# Sheet1_Palm.net
KiCad netlist of a schematic drawn in Altium Designer
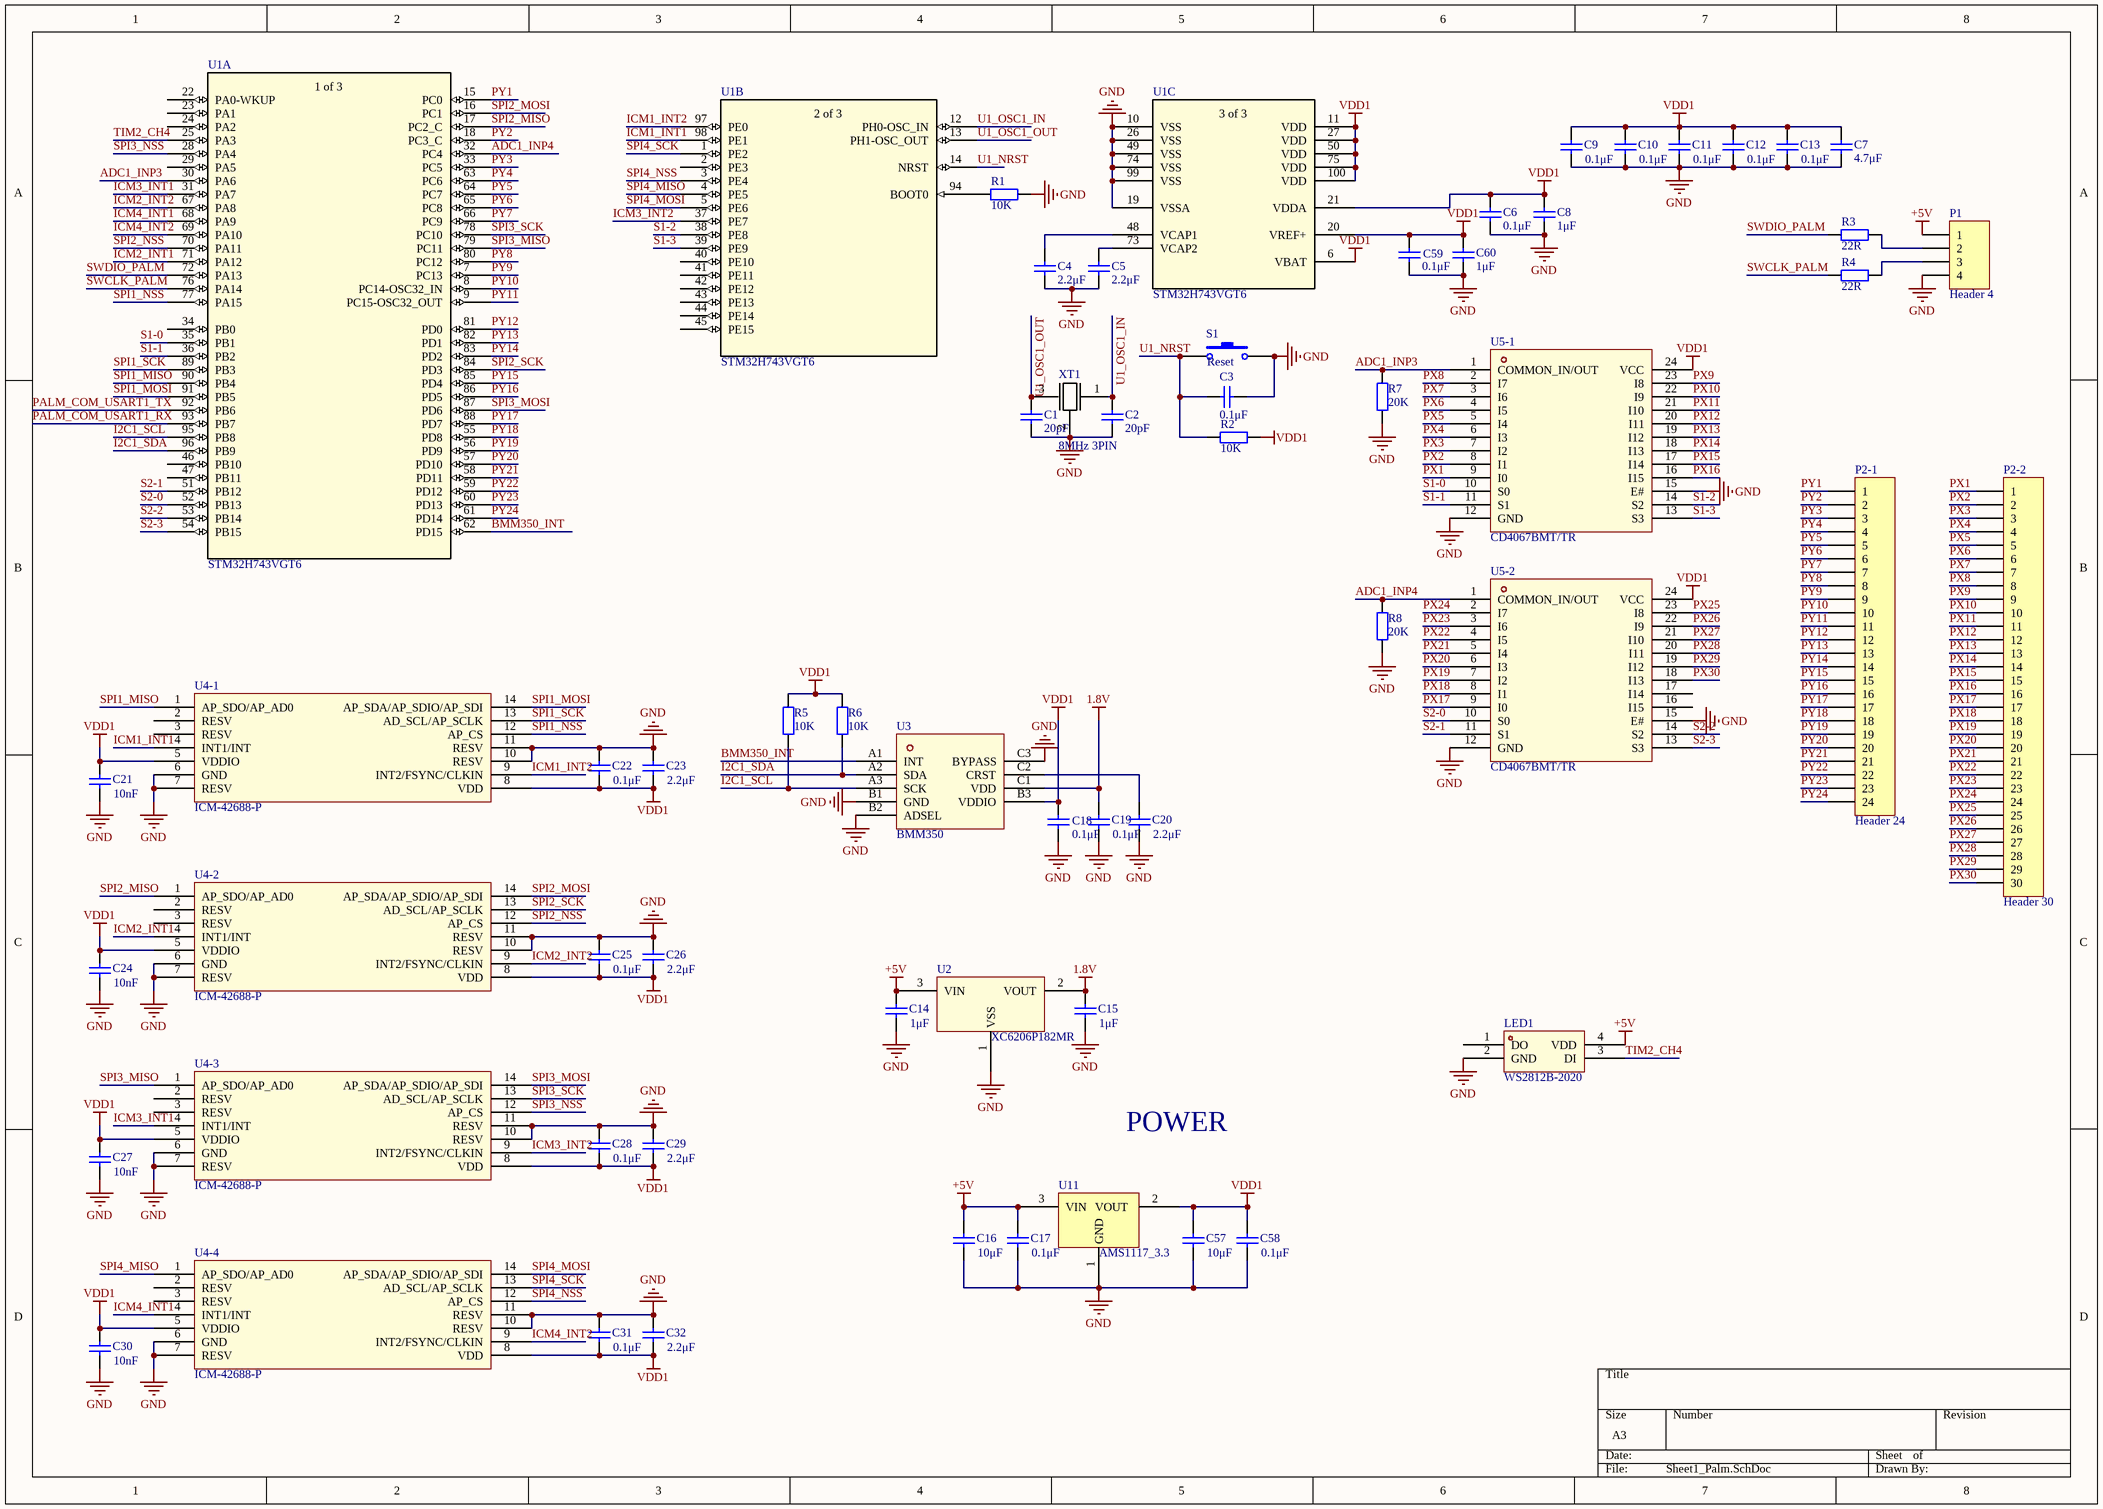
[diagram p0: Sheet1_Palm.SchDoc]

(export (version "E")
  (design (tool "Eeschema 10.0.6"))
  (components
    (comp (ref "C1")
      (value "20pF")
      (footprint "C0402")
      (description "Capacitor (Semiconductor SIM Model)")
      (fields (field (name "PUBLISHER") "Altium Limited"))
      (libsource (lib "Miscellaneous Devices") (part "Cap Semi"))
    )
    (comp (ref "C2")
      (value "20pF")
      (footprint "C0402")
      (description "Capacitor (Semiconductor SIM Model)")
      (fields (field (name "PUBLISHER") "Altium Limited"))
      (libsource (lib "Miscellaneous Devices") (part "Cap Semi"))
    )
    (comp (ref "C3")
      (value "0.1μF")
      (footprint "C0402")
      (description "Capacitor (Semiconductor SIM Model)")
      (fields (field (name "PUBLISHER") "Altium Limited"))
      (libsource (lib "Miscellaneous Devices") (part "Cap Semi"))
    )
    (comp (ref "C4")
      (value "2.2μF")
      (footprint "C0402")
      (description "Capacitor (Semiconductor SIM Model)")
      (fields (field (name "PUBLISHER") "Altium Limited"))
      (libsource (lib "Miscellaneous Devices") (part "Cap Semi"))
    )
    (comp (ref "C5")
      (value "2.2μF")
      (footprint "C0402")
      (description "Capacitor (Semiconductor SIM Model)")
      (fields (field (name "PUBLISHER") "Altium Limited"))
      (libsource (lib "Miscellaneous Devices") (part "Cap Semi"))
    )
    (comp (ref "C6")
      (value "0.1μF")
      (footprint "C0402")
      (description "Capacitor (Semiconductor SIM Model)")
      (fields (field (name "PUBLISHER") "Altium Limited"))
      (libsource (lib "Miscellaneous Devices") (part "Cap Semi"))
    )
    (comp (ref "C7")
      (value "4.7μF")
      (footprint "C0402")
      (description "Capacitor (Semiconductor SIM Model)")
      (fields (field (name "PUBLISHER") "Altium Limited"))
      (libsource (lib "Miscellaneous Devices") (part "Cap Semi"))
    )
    (comp (ref "C8")
      (value "1μF")
      (footprint "C0402")
      (description "Capacitor (Semiconductor SIM Model)")
      (fields (field (name "PUBLISHER") "Altium Limited"))
      (libsource (lib "Miscellaneous Devices") (part "Cap Semi"))
    )
    (comp (ref "C9")
      (value "0.1μF")
      (footprint "C0402")
      (description "Capacitor (Semiconductor SIM Model)")
      (fields (field (name "PUBLISHER") "Altium Limited"))
      (libsource (lib "Miscellaneous Devices") (part "Cap Semi"))
    )
    (comp (ref "C10")
      (value "0.1μF")
      (footprint "C0402")
      (description "Capacitor (Semiconductor SIM Model)")
      (fields (field (name "PUBLISHER") "Altium Limited"))
      (libsource (lib "Miscellaneous Devices") (part "Cap Semi"))
    )
    (comp (ref "C11")
      (value "0.1μF")
      (footprint "C0402")
      (description "Capacitor (Semiconductor SIM Model)")
      (fields (field (name "PUBLISHER") "Altium Limited"))
      (libsource (lib "Miscellaneous Devices") (part "Cap Semi"))
    )
    (comp (ref "C12")
      (value "0.1μF")
      (footprint "C0402")
      (description "Capacitor (Semiconductor SIM Model)")
      (fields (field (name "PUBLISHER") "Altium Limited"))
      (libsource (lib "Miscellaneous Devices") (part "Cap Semi"))
    )
    (comp (ref "C13")
      (value "0.1μF")
      (footprint "C0402")
      (description "Capacitor (Semiconductor SIM Model)")
      (fields (field (name "PUBLISHER") "Altium Limited"))
      (libsource (lib "Miscellaneous Devices") (part "Cap Semi"))
    )
    (comp (ref "C14")
      (value "1μF")
      (footprint "C0402")
      (description "Capacitor (Semiconductor SIM Model)")
      (fields (field (name "PUBLISHER") "Altium Limited"))
      (libsource (lib "Miscellaneous Devices") (part "Cap Semi"))
    )
    (comp (ref "C15")
      (value "1μF")
      (footprint "C0402")
      (description "Capacitor (Semiconductor SIM Model)")
      (fields (field (name "PUBLISHER") "Altium Limited"))
      (libsource (lib "Miscellaneous Devices") (part "Cap Semi"))
    )
    (comp (ref "C16")
      (value "10μF")
      (footprint "C0402")
      (description "Capacitor (Semiconductor SIM Model)")
      (fields (field (name "PUBLISHER") "Altium Limited"))
      (libsource (lib "Miscellaneous Devices") (part "Cap Semi"))
    )
    (comp (ref "C17")
      (value "0.1μF")
      (footprint "C0402")
      (description "Capacitor (Semiconductor SIM Model)")
      (fields (field (name "PUBLISHER") "Altium Limited"))
      (libsource (lib "Miscellaneous Devices") (part "Cap Semi"))
    )
    (comp (ref "C18")
      (value "0.1μF")
      (footprint "C0402")
      (description "Capacitor (Semiconductor SIM Model)")
      (fields (field (name "PUBLISHER") "Altium Limited"))
      (libsource (lib "Miscellaneous Devices") (part "Cap Semi"))
    )
    (comp (ref "C19")
      (value "0.1μF")
      (footprint "C0402")
      (description "Capacitor (Semiconductor SIM Model)")
      (fields (field (name "PUBLISHER") "Altium Limited"))
      (libsource (lib "Miscellaneous Devices") (part "Cap Semi"))
    )
    (comp (ref "C20")
      (value "2.2μF")
      (footprint "C0402")
      (description "Capacitor (Semiconductor SIM Model)")
      (fields (field (name "PUBLISHER") "Altium Limited"))
      (libsource (lib "Miscellaneous Devices") (part "Cap Semi"))
    )
    (comp (ref "C21")
      (value "10nF")
      (footprint "C0402")
      (description "Capacitor (Semiconductor SIM Model)")
      (fields (field (name "PUBLISHER") "Altium Limited"))
      (libsource (lib "Miscellaneous Devices") (part "Cap Semi"))
    )
    (comp (ref "C22")
      (value "0.1μF")
      (footprint "C0402")
      (description "Capacitor (Semiconductor SIM Model)")
      (fields (field (name "PUBLISHER") "Altium Limited"))
      (libsource (lib "Miscellaneous Devices") (part "Cap Semi"))
    )
    (comp (ref "C23")
      (value "2.2μF")
      (footprint "C0402")
      (description "Capacitor (Semiconductor SIM Model)")
      (fields (field (name "PUBLISHER") "Altium Limited"))
      (libsource (lib "Miscellaneous Devices") (part "Cap Semi"))
    )
    (comp (ref "C24")
      (value "10nF")
      (footprint "C0402")
      (description "Capacitor (Semiconductor SIM Model)")
      (fields (field (name "PUBLISHER") "Altium Limited"))
      (libsource (lib "Miscellaneous Devices") (part "Cap Semi"))
    )
    (comp (ref "C25")
      (value "0.1μF")
      (footprint "C0402")
      (description "Capacitor (Semiconductor SIM Model)")
      (fields (field (name "PUBLISHER") "Altium Limited"))
      (libsource (lib "Miscellaneous Devices") (part "Cap Semi"))
    )
    (comp (ref "C26")
      (value "2.2μF")
      (footprint "C0402")
      (description "Capacitor (Semiconductor SIM Model)")
      (fields (field (name "PUBLISHER") "Altium Limited"))
      (libsource (lib "Miscellaneous Devices") (part "Cap Semi"))
    )
    (comp (ref "C27")
      (value "10nF")
      (footprint "C0402")
      (description "Capacitor (Semiconductor SIM Model)")
      (fields (field (name "PUBLISHER") "Altium Limited"))
      (libsource (lib "Miscellaneous Devices") (part "Cap Semi"))
    )
    (comp (ref "C28")
      (value "0.1μF")
      (footprint "C0402")
      (description "Capacitor (Semiconductor SIM Model)")
      (fields (field (name "PUBLISHER") "Altium Limited"))
      (libsource (lib "Miscellaneous Devices") (part "Cap Semi"))
    )
    (comp (ref "C29")
      (value "2.2μF")
      (footprint "C0402")
      (description "Capacitor (Semiconductor SIM Model)")
      (fields (field (name "PUBLISHER") "Altium Limited"))
      (libsource (lib "Miscellaneous Devices") (part "Cap Semi"))
    )
    (comp (ref "C30")
      (value "10nF")
      (footprint "C0402")
      (description "Capacitor (Semiconductor SIM Model)")
      (fields (field (name "PUBLISHER") "Altium Limited"))
      (libsource (lib "Miscellaneous Devices") (part "Cap Semi"))
    )
    (comp (ref "C31")
      (value "0.1μF")
      (footprint "C0402")
      (description "Capacitor (Semiconductor SIM Model)")
      (fields (field (name "PUBLISHER") "Altium Limited"))
      (libsource (lib "Miscellaneous Devices") (part "Cap Semi"))
    )
    (comp (ref "C32")
      (value "2.2μF")
      (footprint "C0402")
      (description "Capacitor (Semiconductor SIM Model)")
      (fields (field (name "PUBLISHER") "Altium Limited"))
      (libsource (lib "Miscellaneous Devices") (part "Cap Semi"))
    )
    (comp (ref "C57")
      (value "10μF")
      (footprint "C0402")
      (description "Capacitor (Semiconductor SIM Model)")
      (fields (field (name "PUBLISHER") "Altium Limited"))
      (libsource (lib "Miscellaneous Devices") (part "Cap Semi"))
    )
    (comp (ref "C58")
      (value "0.1μF")
      (footprint "C0402")
      (description "Capacitor (Semiconductor SIM Model)")
      (fields (field (name "PUBLISHER") "Altium Limited"))
      (libsource (lib "Miscellaneous Devices") (part "Cap Semi"))
    )
    (comp (ref "C59")
      (value "0.1μF")
      (footprint "C0402")
      (description "Capacitor (Semiconductor SIM Model)")
      (fields (field (name "PUBLISHER") "Altium Limited"))
      (libsource (lib "Miscellaneous Devices") (part "Cap Semi"))
    )
    (comp (ref "C60")
      (value "1μF")
      (footprint "C0402")
      (description "Capacitor (Semiconductor SIM Model)")
      (fields (field (name "PUBLISHER") "Altium Limited"))
      (libsource (lib "Miscellaneous Devices") (part "Cap Semi"))
    )
    (comp (ref "LED1")
      (value "WS2812B-2020")
      (footprint "LED-SMD_4P-L2.0-W2.0-TL_WS2812B-2020")
      (libsource (lib "Basic") (part "WS2812B-2020"))
    )
    (comp (ref "P1")
      (value "Header 4")
      (footprint "CONN-SMD_XDWF-0910-04P")
      (description "XDWF-0910-04P")
      (fields (field (name "PUBLISHER") "Altium Limited"))
      (libsource (lib "Miscellaneous Connectors") (part "Header 4"))
    )
    (comp (ref "P2-1")
      (value "Header 24")
      (footprint "FPC-SMD_F0502-B-24-10G-R")
      (description "Header, 24-Pin")
      (fields (field (name "PUBLISHER") "Altium Limited"))
      (libsource (lib "Miscellaneous Connectors") (part "Header 24"))
    )
    (comp (ref "P2-2")
      (value "Header 30")
      (footprint "FPC-SMD_30P-P0.50_HCTL_HC-FPC-05-10-30RLTAG")
      (description "Header, 30-Pin")
      (fields (field (name "PUBLISHER") "Altium Limited"))
      (libsource (lib "Miscellaneous Connectors") (part "Header 30"))
    )
    (comp (ref "R1")
      (value "10K")
      (footprint "R0402")
      (description "Resistor")
      (fields (field (name "PUBLISHER") "Altium Limited"))
      (libsource (lib "") (part "Res2_3"))
    )
    (comp (ref "R2")
      (value "10K")
      (footprint "R0402")
      (description "Resistor")
      (fields (field (name "PUBLISHER") "Altium Limited"))
      (libsource (lib "Miscellaneous Devices") (part "Res2"))
    )
    (comp (ref "R3")
      (value "22R")
      (footprint "R0402")
      (description "Resistor")
      (fields (field (name "PUBLISHER") "Altium Limited"))
      (libsource (lib "Miscellaneous Devices") (part "Res2"))
    )
    (comp (ref "R4")
      (value "22R")
      (footprint "R0402")
      (description "Resistor")
      (fields (field (name "PUBLISHER") "Altium Limited"))
      (libsource (lib "Miscellaneous Devices") (part "Res2"))
    )
    (comp (ref "R5")
      (value "10K")
      (footprint "R0402")
      (description "Resistor")
      (fields (field (name "PUBLISHER") "Altium Limited"))
      (libsource (lib "") (part "Res2_2"))
    )
    (comp (ref "R6")
      (value "10K")
      (footprint "R0402")
      (description "Resistor")
      (fields (field (name "PUBLISHER") "Altium Limited"))
      (libsource (lib "") (part "Res2_2"))
    )
    (comp (ref "R7")
      (value "20K")
      (footprint "R0402")
      (description "Resistor")
      (fields (field (name "PUBLISHER") "Altium Limited"))
      (libsource (lib "") (part "Res2_1"))
    )
    (comp (ref "R8")
      (value "20K")
      (footprint "R0402")
      (description "Resistor")
      (fields (field (name "PUBLISHER") "Altium Limited"))
      (libsource (lib "") (part "Res2_1"))
    )
    (comp (ref "S1")
      (value "Reset")
      (footprint "SW-SMD_L3.9-W3.0-P4.45")
      (description "TS-1088R-02026")
      (fields (field (name "PUBLISHER") "Altium Limited"))
      (libsource (lib "Miscellaneous Devices") (part "SW-PB"))
    )
    (comp (ref "U1")
      (value "STM32H743VGT6")
      (footprint "LQFP100-14x14mm")
      (description "No Description Available")
      (libsource (lib "STM32H743VGT6") (part "STM32H743VGT6"))
    )
    (comp (ref "U2")
      (value "XC6206P182MR")
      (footprint "SOT-23-3_L3.0-W1.7-P0.95-LS2.9-BR")
      (libsource (lib "Power") (part "XC6206P182MR"))
    )
    (comp (ref "U3")
      (value "BMM350")
      (footprint "WLCSP-9_L1.3-W1.3-R3-C3-P0.40-TL")
      (libsource (lib "Sensors") (part "BMM350"))
    )
    (comp (ref "U4-1")
      (value "ICM-42688-P")
      (footprint "LGA-14_L3.0-W2.5-P0.50-TL")
      (libsource (lib "Sensors") (part "ICM-42688-P"))
    )
    (comp (ref "U4-2")
      (value "ICM-42688-P")
      (footprint "LGA-14_L3.0-W2.5-P0.50-TL")
      (libsource (lib "Sensors") (part "ICM-42688-P"))
    )
    (comp (ref "U4-3")
      (value "ICM-42688-P")
      (footprint "LGA-14_L3.0-W2.5-P0.50-TL")
      (libsource (lib "Sensors") (part "ICM-42688-P"))
    )
    (comp (ref "U4-4")
      (value "ICM-42688-P")
      (footprint "LGA-14_L3.0-W2.5-P0.50-TL")
      (libsource (lib "Sensors") (part "ICM-42688-P"))
    )
    (comp (ref "U5-1")
      (value "CD4067BMT/TR")
      (footprint "TSSOP-24_L7.8-W4.4-P0.65-LS6.4-BL_1")
      (libsource (lib "Basic") (part "CD4067BMT/TR"))
    )
    (comp (ref "U5-2")
      (value "CD4067BMT/TR")
      (footprint "TSSOP-24_L7.8-W4.4-P0.65-LS6.4-BL_1")
      (libsource (lib "Basic") (part "CD4067BMT/TR"))
    )
    (comp (ref "U11")
      (value "AMS1117_3.3")
      (footprint "AMS1117-3.3")
      (libsource (lib "Schlib1") (part "AMS1117_3.3 SOT-89"))
    )
    (comp (ref "XT1")
      (value "8MHz 3PIN")
      (footprint "8MHz 0.07% OSC-SMD_3P-L3.2-W1.3-P1.20-L")
      (description "CSTNE8M00GH5C000R0")
      (libsource (lib "Schlibs") (part "8MHz 0.07% 3PIN_1"))
    )
  )
  (nets
    (net (code "1") (name "+5V") (class "Default")
      (node (ref "C14") (pin "2") (pinfunction "2_2") (pintype "passive"))
      (node (ref "C16") (pin "2") (pinfunction "2_2") (pintype "passive"))
      (node (ref "C17") (pin "2") (pinfunction "2_2") (pintype "passive"))
      (node (ref "LED1") (pin "4") (pinfunction "VDD_4") (pintype "passive"))
      (node (ref "P1") (pin "1") (pinfunction "1_1") (pintype "passive"))
      (node (ref "U11") (pin "3") (pinfunction "VIN_3") (pintype "passive"))
      (node (ref "U2") (pin "3") (pinfunction "VIN_3") (pintype "passive"))
    )
    (net (code "2") (name "/ADC1_INP3") (class "Default")
      (node (ref "R7") (pin "2") (pinfunction "2_2") (pintype "passive"))
      (node (ref "U1") (pin "30") (pinfunction "PA6_30") (pintype "bidirectional"))
      (node (ref "U5-1") (pin "1") (pinfunction "COMMON_IN/OUT_1") (pintype "passive"))
    )
    (net (code "3") (name "/ADC1_INP4") (class "Default")
      (node (ref "R8") (pin "2") (pinfunction "2_2") (pintype "passive"))
      (node (ref "U1") (pin "32") (pinfunction "PC4_32") (pintype "bidirectional"))
      (node (ref "U5-2") (pin "1") (pinfunction "COMMON_IN/OUT_1") (pintype "passive"))
    )
    (net (code "4") (name "/BMM350_INT") (class "Default")
      (node (ref "U1") (pin "62") (pinfunction "PD15_62") (pintype "bidirectional"))
      (node (ref "U3") (pin "A1") (pinfunction "INT_A1") (pintype "passive"))
    )
    (net (code "5") (name "/I2C1_SCL") (class "Default")
      (node (ref "R5") (pin "2") (pinfunction "2_2") (pintype "passive"))
      (node (ref "U1") (pin "95") (pinfunction "PB8_95") (pintype "bidirectional"))
      (node (ref "U3") (pin "A3") (pinfunction "SCK_A3") (pintype "passive"))
    )
    (net (code "6") (name "/I2C1_SDA") (class "Default")
      (node (ref "R6") (pin "2") (pinfunction "2_2") (pintype "passive"))
      (node (ref "U1") (pin "96") (pinfunction "PB9_96") (pintype "bidirectional"))
      (node (ref "U3") (pin "A2") (pinfunction "SDA_A2") (pintype "passive"))
    )
    (net (code "7") (name "/ICM1_INT1") (class "Default")
      (node (ref "U1") (pin "98") (pinfunction "PE1_98") (pintype "bidirectional"))
      (node (ref "U4-1") (pin "4") (pinfunction "INT1/INT_4") (pintype "passive"))
    )
    (net (code "8") (name "/ICM1_INT2") (class "Default")
      (node (ref "U1") (pin "97") (pinfunction "PE0_97") (pintype "bidirectional"))
      (node (ref "U4-1") (pin "9") (pinfunction "INT2/FSYNC/CLKIN_9") (pintype "passive"))
    )
    (net (code "9") (name "/ICM2_INT1") (class "Default")
      (node (ref "U1") (pin "71") (pinfunction "PA12_71") (pintype "bidirectional"))
      (node (ref "U4-2") (pin "4") (pinfunction "INT1/INT_4") (pintype "passive"))
    )
    (net (code "10") (name "/ICM2_INT2") (class "Default")
      (node (ref "U1") (pin "67") (pinfunction "PA8_67") (pintype "bidirectional"))
      (node (ref "U4-2") (pin "9") (pinfunction "INT2/FSYNC/CLKIN_9") (pintype "passive"))
    )
    (net (code "11") (name "/ICM3_INT1") (class "Default")
      (node (ref "U1") (pin "31") (pinfunction "PA7_31") (pintype "bidirectional"))
      (node (ref "U4-3") (pin "4") (pinfunction "INT1/INT_4") (pintype "passive"))
    )
    (net (code "12") (name "/ICM3_INT2") (class "Default")
      (node (ref "U1") (pin "37") (pinfunction "PE7_37") (pintype "bidirectional"))
      (node (ref "U4-3") (pin "9") (pinfunction "INT2/FSYNC/CLKIN_9") (pintype "passive"))
    )
    (net (code "13") (name "/ICM4_INT1") (class "Default")
      (node (ref "U1") (pin "68") (pinfunction "PA9_68") (pintype "bidirectional"))
      (node (ref "U4-4") (pin "4") (pinfunction "INT1/INT_4") (pintype "passive"))
    )
    (net (code "14") (name "/ICM4_INT2") (class "Default")
      (node (ref "U1") (pin "69") (pinfunction "PA10_69") (pintype "bidirectional"))
      (node (ref "U4-4") (pin "9") (pinfunction "INT2/FSYNC/CLKIN_9") (pintype "passive"))
    )
    (net (code "15") (name "/PALM_COM_USART1_RX") (class "Default")
      (node (ref "U1") (pin "93") (pinfunction "PB7_93") (pintype "bidirectional"))
    )
    (net (code "16") (name "/PALM_COM_USART1_TX") (class "Default")
      (node (ref "U1") (pin "92") (pinfunction "PB6_92") (pintype "bidirectional"))
    )
    (net (code "17") (name "/PX1") (class "Default")
      (node (ref "P2-2") (pin "1") (pinfunction "1_1") (pintype "passive"))
      (node (ref "U5-1") (pin "9") (pinfunction "I0_9") (pintype "passive"))
    )
    (net (code "18") (name "/PX2") (class "Default")
      (node (ref "P2-2") (pin "2") (pinfunction "2_2") (pintype "passive"))
      (node (ref "U5-1") (pin "8") (pinfunction "I1_8") (pintype "passive"))
    )
    (net (code "19") (name "/PX3") (class "Default")
      (node (ref "P2-2") (pin "3") (pinfunction "3_3") (pintype "passive"))
      (node (ref "U5-1") (pin "7") (pinfunction "I2_7") (pintype "passive"))
    )
    (net (code "20") (name "/PX4") (class "Default")
      (node (ref "P2-2") (pin "4") (pinfunction "4_4") (pintype "passive"))
      (node (ref "U5-1") (pin "6") (pinfunction "I3_6") (pintype "passive"))
    )
    (net (code "21") (name "/PX5") (class "Default")
      (node (ref "P2-2") (pin "5") (pinfunction "5_5") (pintype "passive"))
      (node (ref "U5-1") (pin "5") (pinfunction "I4_5") (pintype "passive"))
    )
    (net (code "22") (name "/PX6") (class "Default")
      (node (ref "P2-2") (pin "6") (pinfunction "6_6") (pintype "passive"))
      (node (ref "U5-1") (pin "4") (pinfunction "I5_4") (pintype "passive"))
    )
    (net (code "23") (name "/PX7") (class "Default")
      (node (ref "P2-2") (pin "7") (pinfunction "7_7") (pintype "passive"))
      (node (ref "U5-1") (pin "3") (pinfunction "I6_3") (pintype "passive"))
    )
    (net (code "24") (name "/PX8") (class "Default")
      (node (ref "P2-2") (pin "8") (pinfunction "8_8") (pintype "passive"))
      (node (ref "U5-1") (pin "2") (pinfunction "I7_2") (pintype "passive"))
    )
    (net (code "25") (name "/PX9") (class "Default")
      (node (ref "P2-2") (pin "9") (pinfunction "9_9") (pintype "passive"))
      (node (ref "U5-1") (pin "23") (pinfunction "I8_23") (pintype "passive"))
    )
    (net (code "26") (name "/PX10") (class "Default")
      (node (ref "P2-2") (pin "10") (pinfunction "10_10") (pintype "passive"))
      (node (ref "U5-1") (pin "22") (pinfunction "I9_22") (pintype "passive"))
    )
    (net (code "27") (name "/PX11") (class "Default")
      (node (ref "P2-2") (pin "11") (pinfunction "11_11") (pintype "passive"))
      (node (ref "U5-1") (pin "21") (pinfunction "I10_21") (pintype "passive"))
    )
    (net (code "28") (name "/PX12") (class "Default")
      (node (ref "P2-2") (pin "12") (pinfunction "12_12") (pintype "passive"))
      (node (ref "U5-1") (pin "20") (pinfunction "I11_20") (pintype "passive"))
    )
    (net (code "29") (name "/PX13") (class "Default")
      (node (ref "P2-2") (pin "13") (pinfunction "13_13") (pintype "passive"))
      (node (ref "U5-1") (pin "19") (pinfunction "I12_19") (pintype "passive"))
    )
    (net (code "30") (name "/PX14") (class "Default")
      (node (ref "P2-2") (pin "14") (pinfunction "14_14") (pintype "passive"))
      (node (ref "U5-1") (pin "18") (pinfunction "I13_18") (pintype "passive"))
    )
    (net (code "31") (name "/PX15") (class "Default")
      (node (ref "P2-2") (pin "15") (pinfunction "15_15") (pintype "passive"))
      (node (ref "U5-1") (pin "17") (pinfunction "I14_17") (pintype "passive"))
    )
    (net (code "32") (name "/PX16") (class "Default")
      (node (ref "P2-2") (pin "16") (pinfunction "16_16") (pintype "passive"))
      (node (ref "U5-1") (pin "16") (pinfunction "I15_16") (pintype "passive"))
    )
    (net (code "33") (name "/PX17") (class "Default")
      (node (ref "P2-2") (pin "17") (pinfunction "17_17") (pintype "passive"))
      (node (ref "U5-2") (pin "9") (pinfunction "I0_9") (pintype "passive"))
    )
    (net (code "34") (name "/PX18") (class "Default")
      (node (ref "P2-2") (pin "18") (pinfunction "18_18") (pintype "passive"))
      (node (ref "U5-2") (pin "8") (pinfunction "I1_8") (pintype "passive"))
    )
    (net (code "35") (name "/PX19") (class "Default")
      (node (ref "P2-2") (pin "19") (pinfunction "19_19") (pintype "passive"))
      (node (ref "U5-2") (pin "7") (pinfunction "I2_7") (pintype "passive"))
    )
    (net (code "36") (name "/PX20") (class "Default")
      (node (ref "P2-2") (pin "20") (pinfunction "20_20") (pintype "passive"))
      (node (ref "U5-2") (pin "6") (pinfunction "I3_6") (pintype "passive"))
    )
    (net (code "37") (name "/PX21") (class "Default")
      (node (ref "P2-2") (pin "21") (pinfunction "21_21") (pintype "passive"))
      (node (ref "U5-2") (pin "5") (pinfunction "I4_5") (pintype "passive"))
    )
    (net (code "38") (name "/PX22") (class "Default")
      (node (ref "P2-2") (pin "22") (pinfunction "22_22") (pintype "passive"))
      (node (ref "U5-2") (pin "4") (pinfunction "I5_4") (pintype "passive"))
    )
    (net (code "39") (name "/PX23") (class "Default")
      (node (ref "P2-2") (pin "23") (pinfunction "23_23") (pintype "passive"))
      (node (ref "U5-2") (pin "3") (pinfunction "I6_3") (pintype "passive"))
    )
    (net (code "40") (name "/PX24") (class "Default")
      (node (ref "P2-2") (pin "24") (pinfunction "24_24") (pintype "passive"))
      (node (ref "U5-2") (pin "2") (pinfunction "I7_2") (pintype "passive"))
    )
    (net (code "41") (name "/PX25") (class "Default")
      (node (ref "P2-2") (pin "25") (pinfunction "25_25") (pintype "passive"))
      (node (ref "U5-2") (pin "23") (pinfunction "I8_23") (pintype "passive"))
    )
    (net (code "42") (name "/PX26") (class "Default")
      (node (ref "P2-2") (pin "26") (pinfunction "26_26") (pintype "passive"))
      (node (ref "U5-2") (pin "22") (pinfunction "I9_22") (pintype "passive"))
    )
    (net (code "43") (name "/PX27") (class "Default")
      (node (ref "P2-2") (pin "27") (pinfunction "27_27") (pintype "passive"))
      (node (ref "U5-2") (pin "21") (pinfunction "I10_21") (pintype "passive"))
    )
    (net (code "44") (name "/PX28") (class "Default")
      (node (ref "P2-2") (pin "28") (pinfunction "28_28") (pintype "passive"))
      (node (ref "U5-2") (pin "20") (pinfunction "I11_20") (pintype "passive"))
    )
    (net (code "45") (name "/PX29") (class "Default")
      (node (ref "P2-2") (pin "29") (pinfunction "29_29") (pintype "passive"))
      (node (ref "U5-2") (pin "19") (pinfunction "I12_19") (pintype "passive"))
    )
    (net (code "46") (name "/PX30") (class "Default")
      (node (ref "P2-2") (pin "30") (pinfunction "30_30") (pintype "passive"))
      (node (ref "U5-2") (pin "18") (pinfunction "I13_18") (pintype "passive"))
    )
    (net (code "47") (name "/PY1") (class "Default")
      (node (ref "P2-1") (pin "1") (pinfunction "1_1") (pintype "passive"))
      (node (ref "U1") (pin "15") (pinfunction "PC0_15") (pintype "bidirectional"))
    )
    (net (code "48") (name "/PY2") (class "Default")
      (node (ref "P2-1") (pin "2") (pinfunction "2_2") (pintype "passive"))
      (node (ref "U1") (pin "18") (pinfunction "PC3_C_18") (pintype "bidirectional"))
    )
    (net (code "49") (name "/PY3") (class "Default")
      (node (ref "P2-1") (pin "3") (pinfunction "3_3") (pintype "passive"))
      (node (ref "U1") (pin "33") (pinfunction "PC5_33") (pintype "bidirectional"))
    )
    (net (code "50") (name "/PY4") (class "Default")
      (node (ref "P2-1") (pin "4") (pinfunction "4_4") (pintype "passive"))
      (node (ref "U1") (pin "63") (pinfunction "PC6_63") (pintype "bidirectional"))
    )
    (net (code "51") (name "/PY5") (class "Default")
      (node (ref "P2-1") (pin "5") (pinfunction "5_5") (pintype "passive"))
      (node (ref "U1") (pin "64") (pinfunction "PC7_64") (pintype "bidirectional"))
    )
    (net (code "52") (name "/PY6") (class "Default")
      (node (ref "P2-1") (pin "6") (pinfunction "6_6") (pintype "passive"))
      (node (ref "U1") (pin "65") (pinfunction "PC8_65") (pintype "bidirectional"))
    )
    (net (code "53") (name "/PY7") (class "Default")
      (node (ref "P2-1") (pin "7") (pinfunction "7_7") (pintype "passive"))
      (node (ref "U1") (pin "66") (pinfunction "PC9_66") (pintype "bidirectional"))
    )
    (net (code "54") (name "/PY8") (class "Default")
      (node (ref "P2-1") (pin "8") (pinfunction "8_8") (pintype "passive"))
      (node (ref "U1") (pin "80") (pinfunction "PC12_80") (pintype "bidirectional"))
    )
    (net (code "55") (name "/PY9") (class "Default")
      (node (ref "P2-1") (pin "9") (pinfunction "9_9") (pintype "passive"))
      (node (ref "U1") (pin "7") (pinfunction "PC13_7") (pintype "bidirectional"))
    )
    (net (code "56") (name "/PY10") (class "Default")
      (node (ref "P2-1") (pin "10") (pinfunction "10_10") (pintype "passive"))
      (node (ref "U1") (pin "8") (pinfunction "PC14-OSC32_IN_8") (pintype "bidirectional"))
    )
    (net (code "57") (name "/PY11") (class "Default")
      (node (ref "P2-1") (pin "11") (pinfunction "11_11") (pintype "passive"))
      (node (ref "U1") (pin "9") (pinfunction "PC15-OSC32_OUT_9") (pintype "bidirectional"))
    )
    (net (code "58") (name "/PY12") (class "Default")
      (node (ref "P2-1") (pin "12") (pinfunction "12_12") (pintype "passive"))
      (node (ref "U1") (pin "81") (pinfunction "PD0_81") (pintype "bidirectional"))
    )
    (net (code "59") (name "/PY13") (class "Default")
      (node (ref "P2-1") (pin "13") (pinfunction "13_13") (pintype "passive"))
      (node (ref "U1") (pin "82") (pinfunction "PD1_82") (pintype "bidirectional"))
    )
    (net (code "60") (name "/PY14") (class "Default")
      (node (ref "P2-1") (pin "14") (pinfunction "14_14") (pintype "passive"))
      (node (ref "U1") (pin "83") (pinfunction "PD2_83") (pintype "bidirectional"))
    )
    (net (code "61") (name "/PY15") (class "Default")
      (node (ref "P2-1") (pin "15") (pinfunction "15_15") (pintype "passive"))
      (node (ref "U1") (pin "85") (pinfunction "PD4_85") (pintype "bidirectional"))
    )
    (net (code "62") (name "/PY16") (class "Default")
      (node (ref "P2-1") (pin "16") (pinfunction "16_16") (pintype "passive"))
      (node (ref "U1") (pin "86") (pinfunction "PD5_86") (pintype "bidirectional"))
    )
    (net (code "63") (name "/PY17") (class "Default")
      (node (ref "P2-1") (pin "17") (pinfunction "17_17") (pintype "passive"))
      (node (ref "U1") (pin "88") (pinfunction "PD7_88") (pintype "bidirectional"))
    )
    (net (code "64") (name "/PY18") (class "Default")
      (node (ref "P2-1") (pin "18") (pinfunction "18_18") (pintype "passive"))
      (node (ref "U1") (pin "55") (pinfunction "PD8_55") (pintype "bidirectional"))
    )
    (net (code "65") (name "/PY19") (class "Default")
      (node (ref "P2-1") (pin "19") (pinfunction "19_19") (pintype "passive"))
      (node (ref "U1") (pin "56") (pinfunction "PD9_56") (pintype "bidirectional"))
    )
    (net (code "66") (name "/PY20") (class "Default")
      (node (ref "P2-1") (pin "20") (pinfunction "20_20") (pintype "passive"))
      (node (ref "U1") (pin "57") (pinfunction "PD10_57") (pintype "bidirectional"))
    )
    (net (code "67") (name "/PY21") (class "Default")
      (node (ref "P2-1") (pin "21") (pinfunction "21_21") (pintype "passive"))
      (node (ref "U1") (pin "58") (pinfunction "PD11_58") (pintype "bidirectional"))
    )
    (net (code "68") (name "/PY22") (class "Default")
      (node (ref "P2-1") (pin "22") (pinfunction "22_22") (pintype "passive"))
      (node (ref "U1") (pin "59") (pinfunction "PD12_59") (pintype "bidirectional"))
    )
    (net (code "69") (name "/PY23") (class "Default")
      (node (ref "P2-1") (pin "23") (pinfunction "23_23") (pintype "passive"))
      (node (ref "U1") (pin "60") (pinfunction "PD13_60") (pintype "bidirectional"))
    )
    (net (code "70") (name "/PY24") (class "Default")
      (node (ref "P2-1") (pin "24") (pinfunction "24_24") (pintype "passive"))
      (node (ref "U1") (pin "61") (pinfunction "PD14_61") (pintype "bidirectional"))
    )
    (net (code "71") (name "/S1-0") (class "Default")
      (node (ref "U1") (pin "35") (pinfunction "PB1_35") (pintype "bidirectional"))
      (node (ref "U5-1") (pin "10") (pinfunction "S0_10") (pintype "passive"))
    )
    (net (code "72") (name "/S1-1") (class "Default")
      (node (ref "U1") (pin "36") (pinfunction "PB2_36") (pintype "bidirectional"))
      (node (ref "U5-1") (pin "11") (pinfunction "S1_11") (pintype "passive"))
    )
    (net (code "73") (name "/S1-2") (class "Default")
      (node (ref "U1") (pin "38") (pinfunction "PE8_38") (pintype "bidirectional"))
      (node (ref "U5-1") (pin "14") (pinfunction "S2_14") (pintype "passive"))
    )
    (net (code "74") (name "/S1-3") (class "Default")
      (node (ref "U1") (pin "39") (pinfunction "PE9_39") (pintype "bidirectional"))
      (node (ref "U5-1") (pin "13") (pinfunction "S3_13") (pintype "passive"))
    )
    (net (code "75") (name "/S2-0") (class "Default")
      (node (ref "U1") (pin "52") (pinfunction "PB13_52") (pintype "bidirectional"))
      (node (ref "U5-2") (pin "10") (pinfunction "S0_10") (pintype "passive"))
    )
    (net (code "76") (name "/S2-1") (class "Default")
      (node (ref "U1") (pin "51") (pinfunction "PB12_51") (pintype "bidirectional"))
      (node (ref "U5-2") (pin "11") (pinfunction "S1_11") (pintype "passive"))
    )
    (net (code "77") (name "/S2-2") (class "Default")
      (node (ref "U1") (pin "53") (pinfunction "PB14_53") (pintype "bidirectional"))
      (node (ref "U5-2") (pin "14") (pinfunction "S2_14") (pintype "passive"))
    )
    (net (code "78") (name "/S2-3") (class "Default")
      (node (ref "U1") (pin "54") (pinfunction "PB15_54") (pintype "bidirectional"))
      (node (ref "U5-2") (pin "13") (pinfunction "S3_13") (pintype "passive"))
    )
    (net (code "79") (name "/SPI1_MISO") (class "Default")
      (node (ref "U1") (pin "90") (pinfunction "PB4_90") (pintype "bidirectional"))
      (node (ref "U4-1") (pin "1") (pinfunction "AP_SDO/AP_AD0_1") (pintype "passive"))
    )
    (net (code "80") (name "/SPI1_MOSI") (class "Default")
      (node (ref "U1") (pin "91") (pinfunction "PB5_91") (pintype "bidirectional"))
      (node (ref "U4-1") (pin "14") (pinfunction "AP_SDA/AP_SDIO/AP_SDI_14") (pintype "passive"))
    )
    (net (code "81") (name "/SPI1_NSS") (class "Default")
      (node (ref "U1") (pin "77") (pinfunction "PA15_77") (pintype "bidirectional"))
      (node (ref "U4-1") (pin "12") (pinfunction "AP_CS_12") (pintype "passive"))
    )
    (net (code "82") (name "/SPI1_SCK") (class "Default")
      (node (ref "U1") (pin "89") (pinfunction "PB3_89") (pintype "bidirectional"))
      (node (ref "U4-1") (pin "13") (pinfunction "AD_SCL/AP_SCLK_13") (pintype "passive"))
    )
    (net (code "83") (name "/SPI2_MISO") (class "Default")
      (node (ref "U1") (pin "17") (pinfunction "PC2_C_17") (pintype "bidirectional"))
      (node (ref "U4-2") (pin "1") (pinfunction "AP_SDO/AP_AD0_1") (pintype "passive"))
    )
    (net (code "84") (name "/SPI2_MOSI") (class "Default")
      (node (ref "U1") (pin "16") (pinfunction "PC1_16") (pintype "bidirectional"))
      (node (ref "U4-2") (pin "14") (pinfunction "AP_SDA/AP_SDIO/AP_SDI_14") (pintype "passive"))
    )
    (net (code "85") (name "/SPI2_NSS") (class "Default")
      (node (ref "U1") (pin "70") (pinfunction "PA11_70") (pintype "bidirectional"))
      (node (ref "U4-2") (pin "12") (pinfunction "AP_CS_12") (pintype "passive"))
    )
    (net (code "86") (name "/SPI2_SCK") (class "Default")
      (node (ref "U1") (pin "84") (pinfunction "PD3_84") (pintype "bidirectional"))
      (node (ref "U4-2") (pin "13") (pinfunction "AD_SCL/AP_SCLK_13") (pintype "passive"))
    )
    (net (code "87") (name "/SPI3_MISO") (class "Default")
      (node (ref "U1") (pin "79") (pinfunction "PC11_79") (pintype "bidirectional"))
      (node (ref "U4-3") (pin "1") (pinfunction "AP_SDO/AP_AD0_1") (pintype "passive"))
    )
    (net (code "88") (name "/SPI3_MOSI") (class "Default")
      (node (ref "U1") (pin "87") (pinfunction "PD6_87") (pintype "bidirectional"))
      (node (ref "U4-3") (pin "14") (pinfunction "AP_SDA/AP_SDIO/AP_SDI_14") (pintype "passive"))
    )
    (net (code "89") (name "/SPI3_NSS") (class "Default")
      (node (ref "U1") (pin "28") (pinfunction "PA4_28") (pintype "bidirectional"))
      (node (ref "U4-3") (pin "12") (pinfunction "AP_CS_12") (pintype "passive"))
    )
    (net (code "90") (name "/SPI3_SCK") (class "Default")
      (node (ref "U1") (pin "78") (pinfunction "PC10_78") (pintype "bidirectional"))
      (node (ref "U4-3") (pin "13") (pinfunction "AD_SCL/AP_SCLK_13") (pintype "passive"))
    )
    (net (code "91") (name "/SPI4_MISO") (class "Default")
      (node (ref "U1") (pin "4") (pinfunction "PE5_4") (pintype "bidirectional"))
      (node (ref "U4-4") (pin "1") (pinfunction "AP_SDO/AP_AD0_1") (pintype "passive"))
    )
    (net (code "92") (name "/SPI4_MOSI") (class "Default")
      (node (ref "U1") (pin "5") (pinfunction "PE6_5") (pintype "bidirectional"))
      (node (ref "U4-4") (pin "14") (pinfunction "AP_SDA/AP_SDIO/AP_SDI_14") (pintype "passive"))
    )
    (net (code "93") (name "/SPI4_NSS") (class "Default")
      (node (ref "U1") (pin "3") (pinfunction "PE4_3") (pintype "bidirectional"))
      (node (ref "U4-4") (pin "12") (pinfunction "AP_CS_12") (pintype "passive"))
    )
    (net (code "94") (name "/SPI4_SCK") (class "Default")
      (node (ref "U1") (pin "1") (pinfunction "PE2_1") (pintype "bidirectional"))
      (node (ref "U4-4") (pin "13") (pinfunction "AD_SCL/AP_SCLK_13") (pintype "passive"))
    )
    (net (code "95") (name "/SWCLK_PALM") (class "Default")
      (node (ref "R4") (pin "1") (pinfunction "1_1") (pintype "passive"))
      (node (ref "U1") (pin "76") (pinfunction "PA14_76") (pintype "bidirectional"))
    )
    (net (code "96") (name "/SWDIO_PALM") (class "Default")
      (node (ref "R3") (pin "1") (pinfunction "1_1") (pintype "passive"))
      (node (ref "U1") (pin "72") (pinfunction "PA13_72") (pintype "bidirectional"))
    )
    (net (code "97") (name "/TIM2_CH4") (class "Default")
      (node (ref "LED1") (pin "3") (pinfunction "DI_3") (pintype "passive"))
      (node (ref "U1") (pin "25") (pinfunction "PA3_25") (pintype "bidirectional"))
    )
    (net (code "98") (name "/U1_NRST") (class "Default")
      (node (ref "C3") (pin "1") (pinfunction "1_1") (pintype "passive"))
      (node (ref "R2") (pin "1") (pinfunction "1_1") (pintype "passive"))
      (node (ref "S1") (pin "1") (pinfunction "1_1") (pintype "passive"))
      (node (ref "U1") (pin "14") (pinfunction "NRST_14") (pintype "bidirectional"))
    )
    (net (code "99") (name "/U1_OSC1_IN") (class "Default")
      (node (ref "C2") (pin "2") (pinfunction "2_2") (pintype "passive"))
      (node (ref "U1") (pin "12") (pinfunction "PH0-OSC_IN_12") (pintype "bidirectional"))
      (node (ref "XT1") (pin "1") (pinfunction "OUTPUT_1") (pintype "passive"))
    )
    (net (code "100") (name "/U1_OSC1_OUT") (class "Default")
      (node (ref "C1") (pin "2") (pinfunction "2_2") (pintype "passive"))
      (node (ref "U1") (pin "13") (pinfunction "PH1-OSC_OUT_13") (pintype "bidirectional"))
      (node (ref "XT1") (pin "3") (pinfunction "INPUT_3") (pintype "passive"))
    )
    (net (code "101") (name "1.8V") (class "Default")
      (node (ref "C15") (pin "2") (pinfunction "2_2") (pintype "passive"))
      (node (ref "C19") (pin "2") (pinfunction "2_2") (pintype "passive"))
      (node (ref "U2") (pin "2") (pinfunction "VOUT_2") (pintype "passive"))
      (node (ref "U3") (pin "C1") (pinfunction "VDD_C1") (pintype "passive"))
    )
    (net (code "102") (name "GND") (class "Default")
      (node (ref "C1") (pin "1") (pinfunction "1_1") (pintype "passive"))
      (node (ref "C10") (pin "1") (pinfunction "1_1") (pintype "passive"))
      (node (ref "C11") (pin "1") (pinfunction "1_1") (pintype "passive"))
      (node (ref "C12") (pin "1") (pinfunction "1_1") (pintype "passive"))
      (node (ref "C13") (pin "1") (pinfunction "1_1") (pintype "passive"))
      (node (ref "C14") (pin "1") (pinfunction "1_1") (pintype "passive"))
      (node (ref "C15") (pin "1") (pinfunction "1_1") (pintype "passive"))
      (node (ref "C16") (pin "1") (pinfunction "1_1") (pintype "passive"))
      (node (ref "C17") (pin "1") (pinfunction "1_1") (pintype "passive"))
      (node (ref "C18") (pin "1") (pinfunction "1_1") (pintype "passive"))
      (node (ref "C19") (pin "1") (pinfunction "1_1") (pintype "passive"))
      (node (ref "C2") (pin "1") (pinfunction "1_1") (pintype "passive"))
      (node (ref "C20") (pin "1") (pinfunction "1_1") (pintype "passive"))
      (node (ref "C21") (pin "1") (pinfunction "1_1") (pintype "passive"))
      (node (ref "C22") (pin "2") (pinfunction "2_2") (pintype "passive"))
      (node (ref "C23") (pin "2") (pinfunction "2_2") (pintype "passive"))
      (node (ref "C24") (pin "1") (pinfunction "1_1") (pintype "passive"))
      (node (ref "C25") (pin "2") (pinfunction "2_2") (pintype "passive"))
      (node (ref "C26") (pin "2") (pinfunction "2_2") (pintype "passive"))
      (node (ref "C27") (pin "1") (pinfunction "1_1") (pintype "passive"))
      (node (ref "C28") (pin "2") (pinfunction "2_2") (pintype "passive"))
      (node (ref "C29") (pin "2") (pinfunction "2_2") (pintype "passive"))
      (node (ref "C3") (pin "2") (pinfunction "2_2") (pintype "passive"))
      (node (ref "C30") (pin "1") (pinfunction "1_1") (pintype "passive"))
      (node (ref "C31") (pin "2") (pinfunction "2_2") (pintype "passive"))
      (node (ref "C32") (pin "2") (pinfunction "2_2") (pintype "passive"))
      (node (ref "C4") (pin "1") (pinfunction "1_1") (pintype "passive"))
      (node (ref "C5") (pin "1") (pinfunction "1_1") (pintype "passive"))
      (node (ref "C57") (pin "1") (pinfunction "1_1") (pintype "passive"))
      (node (ref "C58") (pin "1") (pinfunction "1_1") (pintype "passive"))
      (node (ref "C59") (pin "2") (pinfunction "2_2") (pintype "passive"))
      (node (ref "C6") (pin "2") (pinfunction "2_2") (pintype "passive"))
      (node (ref "C60") (pin "2") (pinfunction "2_2") (pintype "passive"))
      (node (ref "C7") (pin "2") (pinfunction "2_2") (pintype "passive"))
      (node (ref "C8") (pin "2") (pinfunction "2_2") (pintype "passive"))
      (node (ref "C9") (pin "1") (pinfunction "1_1") (pintype "passive"))
      (node (ref "LED1") (pin "2") (pinfunction "GND_2") (pintype "passive"))
      (node (ref "P1") (pin "4") (pinfunction "4_4") (pintype "passive"))
      (node (ref "R1") (pin "1") (pinfunction "1_1") (pintype "passive"))
      (node (ref "R7") (pin "1") (pinfunction "1_1") (pintype "passive"))
      (node (ref "R8") (pin "1") (pinfunction "1_1") (pintype "passive"))
      (node (ref "S1") (pin "2") (pinfunction "2_2") (pintype "passive"))
      (node (ref "U1") (pin "10") (pinfunction "VSS_10") (pintype "power_in"))
      (node (ref "U1") (pin "19") (pinfunction "VSSA_19") (pintype "power_in"))
      (node (ref "U1") (pin "26") (pinfunction "VSS_26") (pintype "power_in"))
      (node (ref "U1") (pin "49") (pinfunction "VSS_49") (pintype "power_in"))
      (node (ref "U1") (pin "74") (pinfunction "VSS_74") (pintype "power_in"))
      (node (ref "U1") (pin "99") (pinfunction "VSS_99") (pintype "power_in"))
      (node (ref "U11") (pin "1") (pinfunction "GND_1") (pintype "passive"))
      (node (ref "U2") (pin "1") (pinfunction "VSS_1") (pintype "passive"))
      (node (ref "U3") (pin "B1") (pinfunction "GND_B1") (pintype "passive"))
      (node (ref "U3") (pin "B2") (pinfunction "ADSEL_B2") (pintype "passive"))
      (node (ref "U3") (pin "C3") (pinfunction "BYPASS_C3") (pintype "passive"))
      (node (ref "U4-1") (pin "10") (pinfunction "RESV_10") (pintype "passive"))
      (node (ref "U4-1") (pin "11") (pinfunction "RESV_11") (pintype "passive"))
      (node (ref "U4-1") (pin "6") (pinfunction "GND_6") (pintype "passive"))
      (node (ref "U4-1") (pin "7") (pinfunction "RESV_7") (pintype "passive"))
      (node (ref "U4-2") (pin "10") (pinfunction "RESV_10") (pintype "passive"))
      (node (ref "U4-2") (pin "11") (pinfunction "RESV_11") (pintype "passive"))
      (node (ref "U4-2") (pin "6") (pinfunction "GND_6") (pintype "passive"))
      (node (ref "U4-2") (pin "7") (pinfunction "RESV_7") (pintype "passive"))
      (node (ref "U4-3") (pin "10") (pinfunction "RESV_10") (pintype "passive"))
      (node (ref "U4-3") (pin "11") (pinfunction "RESV_11") (pintype "passive"))
      (node (ref "U4-3") (pin "6") (pinfunction "GND_6") (pintype "passive"))
      (node (ref "U4-3") (pin "7") (pinfunction "RESV_7") (pintype "passive"))
      (node (ref "U4-4") (pin "10") (pinfunction "RESV_10") (pintype "passive"))
      (node (ref "U4-4") (pin "11") (pinfunction "RESV_11") (pintype "passive"))
      (node (ref "U4-4") (pin "6") (pinfunction "GND_6") (pintype "passive"))
      (node (ref "U4-4") (pin "7") (pinfunction "RESV_7") (pintype "passive"))
      (node (ref "U5-1") (pin "12") (pinfunction "GND_12") (pintype "passive"))
      (node (ref "U5-1") (pin "15") (pinfunction "E#_15") (pintype "passive"))
      (node (ref "U5-2") (pin "12") (pinfunction "GND_12") (pintype "passive"))
      (node (ref "U5-2") (pin "15") (pinfunction "E#_15") (pintype "passive"))
      (node (ref "XT1") (pin "2") (pinfunction "GND_2") (pintype "passive"))
    )
    (net (code "103") (name "Net-(P1-Pad2)") (class "Default")
      (node (ref "P1") (pin "2") (pinfunction "2_2") (pintype "passive"))
      (node (ref "R3") (pin "2") (pinfunction "2_2") (pintype "passive"))
    )
    (net (code "104") (name "Net-(P1-Pad3)") (class "Default")
      (node (ref "P1") (pin "3") (pinfunction "3_3") (pintype "passive"))
      (node (ref "R4") (pin "2") (pinfunction "2_2") (pintype "passive"))
    )
    (net (code "105") (name "Net-(U1B-BOOT0)") (class "Default")
      (node (ref "R1") (pin "2") (pinfunction "2_2") (pintype "passive"))
      (node (ref "U1") (pin "94") (pinfunction "BOOT0_94") (pintype "input"))
    )
    (net (code "106") (name "Net-(U1C-VCAP1)") (class "Default")
      (node (ref "C4") (pin "2") (pinfunction "2_2") (pintype "passive"))
      (node (ref "U1") (pin "48") (pinfunction "VCAP1_48") (pintype "power_in"))
    )
    (net (code "107") (name "Net-(U1C-VCAP2)") (class "Default")
      (node (ref "C5") (pin "2") (pinfunction "2_2") (pintype "passive"))
      (node (ref "U1") (pin "73") (pinfunction "VCAP2_73") (pintype "power_in"))
    )
    (net (code "108") (name "Net-(U3-CRST)") (class "Default")
      (node (ref "C20") (pin "2") (pinfunction "2_2") (pintype "passive"))
      (node (ref "U3") (pin "C2") (pinfunction "CRST_C2") (pintype "passive"))
    )
    (net (code "109") (name "VDD1") (class "Default")
      (node (ref "C10") (pin "2") (pinfunction "2_2") (pintype "passive"))
      (node (ref "C11") (pin "2") (pinfunction "2_2") (pintype "passive"))
      (node (ref "C12") (pin "2") (pinfunction "2_2") (pintype "passive"))
      (node (ref "C13") (pin "2") (pinfunction "2_2") (pintype "passive"))
      (node (ref "C18") (pin "2") (pinfunction "2_2") (pintype "passive"))
      (node (ref "C21") (pin "2") (pinfunction "2_2") (pintype "passive"))
      (node (ref "C22") (pin "1") (pinfunction "1_1") (pintype "passive"))
      (node (ref "C23") (pin "1") (pinfunction "1_1") (pintype "passive"))
      (node (ref "C24") (pin "2") (pinfunction "2_2") (pintype "passive"))
      (node (ref "C25") (pin "1") (pinfunction "1_1") (pintype "passive"))
      (node (ref "C26") (pin "1") (pinfunction "1_1") (pintype "passive"))
      (node (ref "C27") (pin "2") (pinfunction "2_2") (pintype "passive"))
      (node (ref "C28") (pin "1") (pinfunction "1_1") (pintype "passive"))
      (node (ref "C29") (pin "1") (pinfunction "1_1") (pintype "passive"))
      (node (ref "C30") (pin "2") (pinfunction "2_2") (pintype "passive"))
      (node (ref "C31") (pin "1") (pinfunction "1_1") (pintype "passive"))
      (node (ref "C32") (pin "1") (pinfunction "1_1") (pintype "passive"))
      (node (ref "C57") (pin "2") (pinfunction "2_2") (pintype "passive"))
      (node (ref "C58") (pin "2") (pinfunction "2_2") (pintype "passive"))
      (node (ref "C59") (pin "1") (pinfunction "1_1") (pintype "passive"))
      (node (ref "C6") (pin "1") (pinfunction "1_1") (pintype "passive"))
      (node (ref "C60") (pin "1") (pinfunction "1_1") (pintype "passive"))
      (node (ref "C7") (pin "1") (pinfunction "1_1") (pintype "passive"))
      (node (ref "C8") (pin "1") (pinfunction "1_1") (pintype "passive"))
      (node (ref "C9") (pin "2") (pinfunction "2_2") (pintype "passive"))
      (node (ref "R2") (pin "2") (pinfunction "2_2") (pintype "passive"))
      (node (ref "R5") (pin "1") (pinfunction "1_1") (pintype "passive"))
      (node (ref "R6") (pin "1") (pinfunction "1_1") (pintype "passive"))
      (node (ref "U1") (pin "100") (pinfunction "VDD_100") (pintype "power_in"))
      (node (ref "U1") (pin "11") (pinfunction "VDD_11") (pintype "power_in"))
      (node (ref "U1") (pin "20") (pinfunction "VREF+_20") (pintype "power_in"))
      (node (ref "U1") (pin "21") (pinfunction "VDDA_21") (pintype "power_in"))
      (node (ref "U1") (pin "27") (pinfunction "VDD_27") (pintype "power_in"))
      (node (ref "U1") (pin "50") (pinfunction "VDD_50") (pintype "power_in"))
      (node (ref "U1") (pin "6") (pinfunction "VBAT_6") (pintype "power_in"))
      (node (ref "U1") (pin "75") (pinfunction "VDD_75") (pintype "power_in"))
      (node (ref "U11") (pin "2") (pinfunction "VOUT_2") (pintype "passive"))
      (node (ref "U3") (pin "B3") (pinfunction "VDDIO_B3") (pintype "passive"))
      (node (ref "U4-1") (pin "5") (pinfunction "VDDIO_5") (pintype "passive"))
      (node (ref "U4-1") (pin "8") (pinfunction "VDD_8") (pintype "passive"))
      (node (ref "U4-2") (pin "5") (pinfunction "VDDIO_5") (pintype "passive"))
      (node (ref "U4-2") (pin "8") (pinfunction "VDD_8") (pintype "passive"))
      (node (ref "U4-3") (pin "5") (pinfunction "VDDIO_5") (pintype "passive"))
      (node (ref "U4-3") (pin "8") (pinfunction "VDD_8") (pintype "passive"))
      (node (ref "U4-4") (pin "5") (pinfunction "VDDIO_5") (pintype "passive"))
      (node (ref "U4-4") (pin "8") (pinfunction "VDD_8") (pintype "passive"))
      (node (ref "U5-1") (pin "24") (pinfunction "VCC_24") (pintype "passive"))
      (node (ref "U5-2") (pin "24") (pinfunction "VCC_24") (pintype "passive"))
    )
    (net (code "110") (name "unconnected-(LED1-DO-Pad1)") (class "Default")
      (node (ref "LED1") (pin "1") (pinfunction "DO_1") (pintype "passive"))
    )
    (net (code "111") (name "unconnected-(U1A-PA0-WKUP-Pad22)") (class "Default")
      (node (ref "U1") (pin "22") (pinfunction "PA0-WKUP_22") (pintype "bidirectional"))
    )
    (net (code "112") (name "unconnected-(U1A-PA1-Pad23)") (class "Default")
      (node (ref "U1") (pin "23") (pinfunction "PA1_23") (pintype "bidirectional"))
    )
    (net (code "113") (name "unconnected-(U1A-PA2-Pad24)") (class "Default")
      (node (ref "U1") (pin "24") (pinfunction "PA2_24") (pintype "bidirectional"))
    )
    (net (code "114") (name "unconnected-(U1A-PA5-Pad29)") (class "Default")
      (node (ref "U1") (pin "29") (pinfunction "PA5_29") (pintype "bidirectional"))
    )
    (net (code "115") (name "unconnected-(U1A-PB0-Pad34)") (class "Default")
      (node (ref "U1") (pin "34") (pinfunction "PB0_34") (pintype "bidirectional"))
    )
    (net (code "116") (name "unconnected-(U1A-PB10-Pad46)") (class "Default")
      (node (ref "U1") (pin "46") (pinfunction "PB10_46") (pintype "bidirectional"))
    )
    (net (code "117") (name "unconnected-(U1A-PB11-Pad47)") (class "Default")
      (node (ref "U1") (pin "47") (pinfunction "PB11_47") (pintype "bidirectional"))
    )
    (net (code "118") (name "unconnected-(U1B-PE3-Pad2)") (class "Default")
      (node (ref "U1") (pin "2") (pinfunction "PE3_2") (pintype "bidirectional"))
    )
    (net (code "119") (name "unconnected-(U1B-PE10-Pad40)") (class "Default")
      (node (ref "U1") (pin "40") (pinfunction "PE10_40") (pintype "bidirectional"))
    )
    (net (code "120") (name "unconnected-(U1B-PE11-Pad41)") (class "Default")
      (node (ref "U1") (pin "41") (pinfunction "PE11_41") (pintype "bidirectional"))
    )
    (net (code "121") (name "unconnected-(U1B-PE12-Pad42)") (class "Default")
      (node (ref "U1") (pin "42") (pinfunction "PE12_42") (pintype "bidirectional"))
    )
    (net (code "122") (name "unconnected-(U1B-PE13-Pad43)") (class "Default")
      (node (ref "U1") (pin "43") (pinfunction "PE13_43") (pintype "bidirectional"))
    )
    (net (code "123") (name "unconnected-(U1B-PE14-Pad44)") (class "Default")
      (node (ref "U1") (pin "44") (pinfunction "PE14_44") (pintype "bidirectional"))
    )
    (net (code "124") (name "unconnected-(U1B-PE15-Pad45)") (class "Default")
      (node (ref "U1") (pin "45") (pinfunction "PE15_45") (pintype "bidirectional"))
    )
    (net (code "125") (name "unconnected-(U4-1-RESV-Pad2)") (class "Default")
      (node (ref "U4-1") (pin "2") (pinfunction "RESV_2") (pintype "passive"))
    )
    (net (code "126") (name "unconnected-(U4-1-RESV-Pad3)") (class "Default")
      (node (ref "U4-1") (pin "3") (pinfunction "RESV_3") (pintype "passive"))
    )
    (net (code "127") (name "unconnected-(U4-2-RESV-Pad2)") (class "Default")
      (node (ref "U4-2") (pin "2") (pinfunction "RESV_2") (pintype "passive"))
    )
    (net (code "128") (name "unconnected-(U4-2-RESV-Pad3)") (class "Default")
      (node (ref "U4-2") (pin "3") (pinfunction "RESV_3") (pintype "passive"))
    )
    (net (code "129") (name "unconnected-(U4-3-RESV-Pad2)") (class "Default")
      (node (ref "U4-3") (pin "2") (pinfunction "RESV_2") (pintype "passive"))
    )
    (net (code "130") (name "unconnected-(U4-3-RESV-Pad3)") (class "Default")
      (node (ref "U4-3") (pin "3") (pinfunction "RESV_3") (pintype "passive"))
    )
    (net (code "131") (name "unconnected-(U4-4-RESV-Pad2)") (class "Default")
      (node (ref "U4-4") (pin "2") (pinfunction "RESV_2") (pintype "passive"))
    )
    (net (code "132") (name "unconnected-(U4-4-RESV-Pad3)") (class "Default")
      (node (ref "U4-4") (pin "3") (pinfunction "RESV_3") (pintype "passive"))
    )
    (net (code "133") (name "unconnected-(U5-2-I14-Pad17)") (class "Default")
      (node (ref "U5-2") (pin "17") (pinfunction "I14_17") (pintype "passive"))
    )
    (net (code "134") (name "unconnected-(U5-2-I15-Pad16)") (class "Default")
      (node (ref "U5-2") (pin "16") (pinfunction "I15_16") (pintype "passive"))
    )
  )
)
